# NUMATO_HDR.net
KiCad netlist of a schematic drawn in Altium Designer
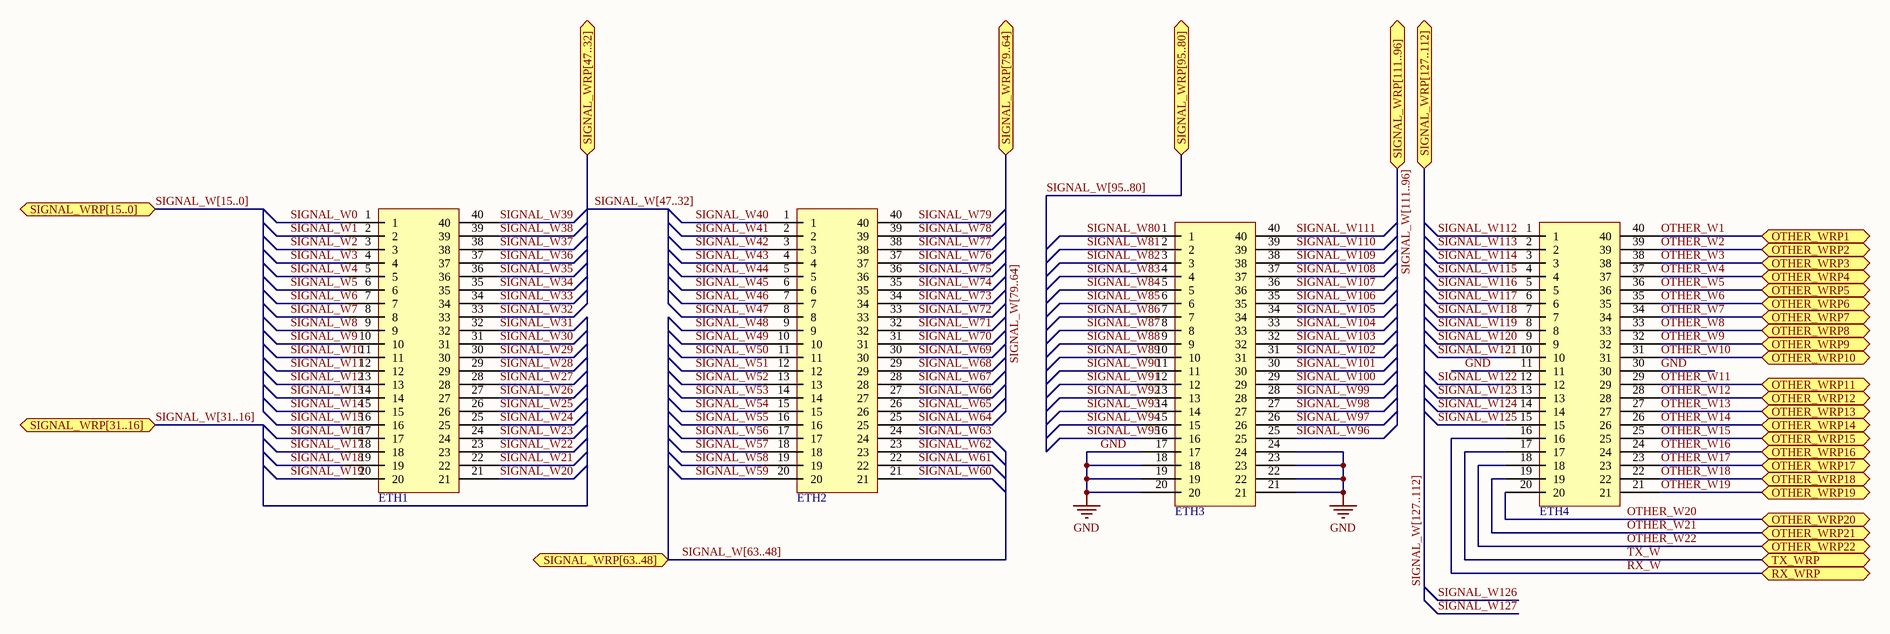
[diagram p0: NUMATO_HDR.SchDoc]

(export (version "E")
  (design (tool "Eeschema 10.0.6"))
  (components
    (comp (ref "ETH1")
      (value "ADAFRUIT_HEADER")
      (footprint "FEMALE_HEADER_SMD")
      (description "Extra tall female header (SMD)")
      (libsource (lib "BBB_Board") (part "ADAFRUIT_HEADER"))
    )
    (comp (ref "ETH2")
      (value "ADAFRUIT_HEADER")
      (footprint "FEMALE_HEADER_SMD")
      (description "Extra tall female header (SMD)")
      (libsource (lib "BBB_Board") (part "ADAFRUIT_HEADER"))
    )
    (comp (ref "ETH3")
      (value "ADAFRUIT_HEADER")
      (footprint "FEMALE_HEADER_SMD")
      (description "Extra tall female header (SMD)")
      (libsource (lib "BBB_Board") (part "ADAFRUIT_HEADER"))
    )
    (comp (ref "ETH4")
      (value "ADAFRUIT_HEADER")
      (footprint "FEMALE_HEADER_SMD")
      (description "Extra tall female header (SMD)")
      (libsource (lib "BBB_Board") (part "ADAFRUIT_HEADER"))
    )
  )
  (nets
    (net (code "1") (name "/OTHER_W1") (class "Default")
      (node (ref "ETH4") (pin "40") (pinfunction "40_40") (pintype "passive"))
    )
    (net (code "2") (name "/OTHER_W2") (class "Default")
      (node (ref "ETH4") (pin "39") (pinfunction "39_39") (pintype "passive"))
    )
    (net (code "3") (name "/OTHER_W3") (class "Default")
      (node (ref "ETH4") (pin "38") (pinfunction "38_38") (pintype "passive"))
    )
    (net (code "4") (name "/OTHER_W4") (class "Default")
      (node (ref "ETH4") (pin "37") (pinfunction "37_37") (pintype "passive"))
    )
    (net (code "5") (name "/OTHER_W5") (class "Default")
      (node (ref "ETH4") (pin "36") (pinfunction "36_36") (pintype "passive"))
    )
    (net (code "6") (name "/OTHER_W6") (class "Default")
      (node (ref "ETH4") (pin "35") (pinfunction "35_35") (pintype "passive"))
    )
    (net (code "7") (name "/OTHER_W7") (class "Default")
      (node (ref "ETH4") (pin "34") (pinfunction "34_34") (pintype "passive"))
    )
    (net (code "8") (name "/OTHER_W8") (class "Default")
      (node (ref "ETH4") (pin "33") (pinfunction "33_33") (pintype "passive"))
    )
    (net (code "9") (name "/OTHER_W9") (class "Default")
      (node (ref "ETH4") (pin "32") (pinfunction "32_32") (pintype "passive"))
    )
    (net (code "10") (name "/OTHER_W10") (class "Default")
      (node (ref "ETH4") (pin "31") (pinfunction "31_31") (pintype "passive"))
    )
    (net (code "11") (name "/OTHER_W11") (class "Default")
      (node (ref "ETH4") (pin "29") (pinfunction "29_29") (pintype "passive"))
    )
    (net (code "12") (name "/OTHER_W12") (class "Default")
      (node (ref "ETH4") (pin "28") (pinfunction "28_28") (pintype "passive"))
    )
    (net (code "13") (name "/OTHER_W13") (class "Default")
      (node (ref "ETH4") (pin "27") (pinfunction "27_27") (pintype "passive"))
    )
    (net (code "14") (name "/OTHER_W14") (class "Default")
      (node (ref "ETH4") (pin "26") (pinfunction "26_26") (pintype "passive"))
    )
    (net (code "15") (name "/OTHER_W15") (class "Default")
      (node (ref "ETH4") (pin "25") (pinfunction "25_25") (pintype "passive"))
    )
    (net (code "16") (name "/OTHER_W16") (class "Default")
      (node (ref "ETH4") (pin "24") (pinfunction "24_24") (pintype "passive"))
    )
    (net (code "17") (name "/OTHER_W17") (class "Default")
      (node (ref "ETH4") (pin "23") (pinfunction "23_23") (pintype "passive"))
    )
    (net (code "18") (name "/OTHER_W18") (class "Default")
      (node (ref "ETH4") (pin "22") (pinfunction "22_22") (pintype "passive"))
    )
    (net (code "19") (name "/OTHER_W19") (class "Default")
      (node (ref "ETH4") (pin "21") (pinfunction "21_21") (pintype "passive"))
    )
    (net (code "20") (name "/OTHER_W20") (class "Default")
      (node (ref "ETH4") (pin "20") (pinfunction "20_20") (pintype "passive"))
    )
    (net (code "21") (name "/OTHER_W21") (class "Default")
      (node (ref "ETH4") (pin "19") (pinfunction "19_19") (pintype "passive"))
    )
    (net (code "22") (name "/OTHER_W22") (class "Default")
      (node (ref "ETH4") (pin "18") (pinfunction "18_18") (pintype "passive"))
    )
    (net (code "23") (name "/RX_W") (class "Default")
      (node (ref "ETH4") (pin "16") (pinfunction "16_16") (pintype "passive"))
    )
    (net (code "24") (name "/SIGNAL_W0") (class "Default")
      (node (ref "ETH1") (pin "1") (pinfunction "1_1") (pintype "passive"))
    )
    (net (code "25") (name "/SIGNAL_W1") (class "Default")
      (node (ref "ETH1") (pin "2") (pinfunction "2_2") (pintype "passive"))
    )
    (net (code "26") (name "/SIGNAL_W2") (class "Default")
      (node (ref "ETH1") (pin "3") (pinfunction "3_3") (pintype "passive"))
    )
    (net (code "27") (name "/SIGNAL_W3") (class "Default")
      (node (ref "ETH1") (pin "4") (pinfunction "4_4") (pintype "passive"))
    )
    (net (code "28") (name "/SIGNAL_W4") (class "Default")
      (node (ref "ETH1") (pin "5") (pinfunction "5_5") (pintype "passive"))
    )
    (net (code "29") (name "/SIGNAL_W5") (class "Default")
      (node (ref "ETH1") (pin "6") (pinfunction "6_6") (pintype "passive"))
    )
    (net (code "30") (name "/SIGNAL_W6") (class "Default")
      (node (ref "ETH1") (pin "7") (pinfunction "7_7") (pintype "passive"))
    )
    (net (code "31") (name "/SIGNAL_W7") (class "Default")
      (node (ref "ETH1") (pin "8") (pinfunction "8_8") (pintype "passive"))
    )
    (net (code "32") (name "/SIGNAL_W8") (class "Default")
      (node (ref "ETH1") (pin "9") (pinfunction "9_9") (pintype "passive"))
    )
    (net (code "33") (name "/SIGNAL_W9") (class "Default")
      (node (ref "ETH1") (pin "10") (pinfunction "10_10") (pintype "passive"))
    )
    (net (code "34") (name "/SIGNAL_W10") (class "Default")
      (node (ref "ETH1") (pin "11") (pinfunction "11_11") (pintype "passive"))
    )
    (net (code "35") (name "/SIGNAL_W11") (class "Default")
      (node (ref "ETH1") (pin "12") (pinfunction "12_12") (pintype "passive"))
    )
    (net (code "36") (name "/SIGNAL_W12") (class "Default")
      (node (ref "ETH1") (pin "13") (pinfunction "13_13") (pintype "passive"))
    )
    (net (code "37") (name "/SIGNAL_W13") (class "Default")
      (node (ref "ETH1") (pin "14") (pinfunction "14_14") (pintype "passive"))
    )
    (net (code "38") (name "/SIGNAL_W14") (class "Default")
      (node (ref "ETH1") (pin "15") (pinfunction "15_15") (pintype "passive"))
    )
    (net (code "39") (name "/SIGNAL_W15") (class "Default")
      (node (ref "ETH1") (pin "16") (pinfunction "16_16") (pintype "passive"))
    )
    (net (code "40") (name "/SIGNAL_W16") (class "Default")
      (node (ref "ETH1") (pin "17") (pinfunction "17_17") (pintype "passive"))
    )
    (net (code "41") (name "/SIGNAL_W17") (class "Default")
      (node (ref "ETH1") (pin "18") (pinfunction "18_18") (pintype "passive"))
    )
    (net (code "42") (name "/SIGNAL_W18") (class "Default")
      (node (ref "ETH1") (pin "19") (pinfunction "19_19") (pintype "passive"))
    )
    (net (code "43") (name "/SIGNAL_W19") (class "Default")
      (node (ref "ETH1") (pin "20") (pinfunction "20_20") (pintype "passive"))
    )
    (net (code "44") (name "/SIGNAL_W20") (class "Default")
      (node (ref "ETH1") (pin "21") (pinfunction "21_21") (pintype "passive"))
    )
    (net (code "45") (name "/SIGNAL_W21") (class "Default")
      (node (ref "ETH1") (pin "22") (pinfunction "22_22") (pintype "passive"))
    )
    (net (code "46") (name "/SIGNAL_W22") (class "Default")
      (node (ref "ETH1") (pin "23") (pinfunction "23_23") (pintype "passive"))
    )
    (net (code "47") (name "/SIGNAL_W23") (class "Default")
      (node (ref "ETH1") (pin "24") (pinfunction "24_24") (pintype "passive"))
    )
    (net (code "48") (name "/SIGNAL_W24") (class "Default")
      (node (ref "ETH1") (pin "25") (pinfunction "25_25") (pintype "passive"))
    )
    (net (code "49") (name "/SIGNAL_W25") (class "Default")
      (node (ref "ETH1") (pin "26") (pinfunction "26_26") (pintype "passive"))
    )
    (net (code "50") (name "/SIGNAL_W26") (class "Default")
      (node (ref "ETH1") (pin "27") (pinfunction "27_27") (pintype "passive"))
    )
    (net (code "51") (name "/SIGNAL_W27") (class "Default")
      (node (ref "ETH1") (pin "28") (pinfunction "28_28") (pintype "passive"))
    )
    (net (code "52") (name "/SIGNAL_W28") (class "Default")
      (node (ref "ETH1") (pin "29") (pinfunction "29_29") (pintype "passive"))
    )
    (net (code "53") (name "/SIGNAL_W29") (class "Default")
      (node (ref "ETH1") (pin "30") (pinfunction "30_30") (pintype "passive"))
    )
    (net (code "54") (name "/SIGNAL_W30") (class "Default")
      (node (ref "ETH1") (pin "31") (pinfunction "31_31") (pintype "passive"))
    )
    (net (code "55") (name "/SIGNAL_W31") (class "Default")
      (node (ref "ETH1") (pin "32") (pinfunction "32_32") (pintype "passive"))
    )
    (net (code "56") (name "/SIGNAL_W32") (class "Default")
      (node (ref "ETH1") (pin "33") (pinfunction "33_33") (pintype "passive"))
    )
    (net (code "57") (name "/SIGNAL_W33") (class "Default")
      (node (ref "ETH1") (pin "34") (pinfunction "34_34") (pintype "passive"))
    )
    (net (code "58") (name "/SIGNAL_W34") (class "Default")
      (node (ref "ETH1") (pin "35") (pinfunction "35_35") (pintype "passive"))
    )
    (net (code "59") (name "/SIGNAL_W35") (class "Default")
      (node (ref "ETH1") (pin "36") (pinfunction "36_36") (pintype "passive"))
    )
    (net (code "60") (name "/SIGNAL_W36") (class "Default")
      (node (ref "ETH1") (pin "37") (pinfunction "37_37") (pintype "passive"))
    )
    (net (code "61") (name "/SIGNAL_W37") (class "Default")
      (node (ref "ETH1") (pin "38") (pinfunction "38_38") (pintype "passive"))
    )
    (net (code "62") (name "/SIGNAL_W38") (class "Default")
      (node (ref "ETH1") (pin "39") (pinfunction "39_39") (pintype "passive"))
    )
    (net (code "63") (name "/SIGNAL_W39") (class "Default")
      (node (ref "ETH1") (pin "40") (pinfunction "40_40") (pintype "passive"))
    )
    (net (code "64") (name "/SIGNAL_W40") (class "Default")
      (node (ref "ETH2") (pin "1") (pinfunction "1_1") (pintype "passive"))
    )
    (net (code "65") (name "/SIGNAL_W41") (class "Default")
      (node (ref "ETH2") (pin "2") (pinfunction "2_2") (pintype "passive"))
    )
    (net (code "66") (name "/SIGNAL_W42") (class "Default")
      (node (ref "ETH2") (pin "3") (pinfunction "3_3") (pintype "passive"))
    )
    (net (code "67") (name "/SIGNAL_W43") (class "Default")
      (node (ref "ETH2") (pin "4") (pinfunction "4_4") (pintype "passive"))
    )
    (net (code "68") (name "/SIGNAL_W44") (class "Default")
      (node (ref "ETH2") (pin "5") (pinfunction "5_5") (pintype "passive"))
    )
    (net (code "69") (name "/SIGNAL_W45") (class "Default")
      (node (ref "ETH2") (pin "6") (pinfunction "6_6") (pintype "passive"))
    )
    (net (code "70") (name "/SIGNAL_W46") (class "Default")
      (node (ref "ETH2") (pin "7") (pinfunction "7_7") (pintype "passive"))
    )
    (net (code "71") (name "/SIGNAL_W47") (class "Default")
      (node (ref "ETH2") (pin "8") (pinfunction "8_8") (pintype "passive"))
    )
    (net (code "72") (name "/SIGNAL_W48") (class "Default")
      (node (ref "ETH2") (pin "9") (pinfunction "9_9") (pintype "passive"))
    )
    (net (code "73") (name "/SIGNAL_W49") (class "Default")
      (node (ref "ETH2") (pin "10") (pinfunction "10_10") (pintype "passive"))
    )
    (net (code "74") (name "/SIGNAL_W50") (class "Default")
      (node (ref "ETH2") (pin "11") (pinfunction "11_11") (pintype "passive"))
    )
    (net (code "75") (name "/SIGNAL_W51") (class "Default")
      (node (ref "ETH2") (pin "12") (pinfunction "12_12") (pintype "passive"))
    )
    (net (code "76") (name "/SIGNAL_W52") (class "Default")
      (node (ref "ETH2") (pin "13") (pinfunction "13_13") (pintype "passive"))
    )
    (net (code "77") (name "/SIGNAL_W53") (class "Default")
      (node (ref "ETH2") (pin "14") (pinfunction "14_14") (pintype "passive"))
    )
    (net (code "78") (name "/SIGNAL_W54") (class "Default")
      (node (ref "ETH2") (pin "15") (pinfunction "15_15") (pintype "passive"))
    )
    (net (code "79") (name "/SIGNAL_W55") (class "Default")
      (node (ref "ETH2") (pin "16") (pinfunction "16_16") (pintype "passive"))
    )
    (net (code "80") (name "/SIGNAL_W56") (class "Default")
      (node (ref "ETH2") (pin "17") (pinfunction "17_17") (pintype "passive"))
    )
    (net (code "81") (name "/SIGNAL_W57") (class "Default")
      (node (ref "ETH2") (pin "18") (pinfunction "18_18") (pintype "passive"))
    )
    (net (code "82") (name "/SIGNAL_W58") (class "Default")
      (node (ref "ETH2") (pin "19") (pinfunction "19_19") (pintype "passive"))
    )
    (net (code "83") (name "/SIGNAL_W59") (class "Default")
      (node (ref "ETH2") (pin "20") (pinfunction "20_20") (pintype "passive"))
    )
    (net (code "84") (name "/SIGNAL_W60") (class "Default")
      (node (ref "ETH2") (pin "21") (pinfunction "21_21") (pintype "passive"))
    )
    (net (code "85") (name "/SIGNAL_W61") (class "Default")
      (node (ref "ETH2") (pin "22") (pinfunction "22_22") (pintype "passive"))
    )
    (net (code "86") (name "/SIGNAL_W62") (class "Default")
      (node (ref "ETH2") (pin "23") (pinfunction "23_23") (pintype "passive"))
    )
    (net (code "87") (name "/SIGNAL_W63") (class "Default")
      (node (ref "ETH2") (pin "24") (pinfunction "24_24") (pintype "passive"))
    )
    (net (code "88") (name "/SIGNAL_W64") (class "Default")
      (node (ref "ETH2") (pin "25") (pinfunction "25_25") (pintype "passive"))
    )
    (net (code "89") (name "/SIGNAL_W65") (class "Default")
      (node (ref "ETH2") (pin "26") (pinfunction "26_26") (pintype "passive"))
    )
    (net (code "90") (name "/SIGNAL_W66") (class "Default")
      (node (ref "ETH2") (pin "27") (pinfunction "27_27") (pintype "passive"))
    )
    (net (code "91") (name "/SIGNAL_W67") (class "Default")
      (node (ref "ETH2") (pin "28") (pinfunction "28_28") (pintype "passive"))
    )
    (net (code "92") (name "/SIGNAL_W68") (class "Default")
      (node (ref "ETH2") (pin "29") (pinfunction "29_29") (pintype "passive"))
    )
    (net (code "93") (name "/SIGNAL_W69") (class "Default")
      (node (ref "ETH2") (pin "30") (pinfunction "30_30") (pintype "passive"))
    )
    (net (code "94") (name "/SIGNAL_W70") (class "Default")
      (node (ref "ETH2") (pin "31") (pinfunction "31_31") (pintype "passive"))
    )
    (net (code "95") (name "/SIGNAL_W71") (class "Default")
      (node (ref "ETH2") (pin "32") (pinfunction "32_32") (pintype "passive"))
    )
    (net (code "96") (name "/SIGNAL_W72") (class "Default")
      (node (ref "ETH2") (pin "33") (pinfunction "33_33") (pintype "passive"))
    )
    (net (code "97") (name "/SIGNAL_W73") (class "Default")
      (node (ref "ETH2") (pin "34") (pinfunction "34_34") (pintype "passive"))
    )
    (net (code "98") (name "/SIGNAL_W74") (class "Default")
      (node (ref "ETH2") (pin "35") (pinfunction "35_35") (pintype "passive"))
    )
    (net (code "99") (name "/SIGNAL_W75") (class "Default")
      (node (ref "ETH2") (pin "36") (pinfunction "36_36") (pintype "passive"))
    )
    (net (code "100") (name "/SIGNAL_W76") (class "Default")
      (node (ref "ETH2") (pin "37") (pinfunction "37_37") (pintype "passive"))
    )
    (net (code "101") (name "/SIGNAL_W77") (class "Default")
      (node (ref "ETH2") (pin "38") (pinfunction "38_38") (pintype "passive"))
    )
    (net (code "102") (name "/SIGNAL_W78") (class "Default")
      (node (ref "ETH2") (pin "39") (pinfunction "39_39") (pintype "passive"))
    )
    (net (code "103") (name "/SIGNAL_W79") (class "Default")
      (node (ref "ETH2") (pin "40") (pinfunction "40_40") (pintype "passive"))
    )
    (net (code "104") (name "/SIGNAL_W80") (class "Default")
      (node (ref "ETH3") (pin "1") (pinfunction "1_1") (pintype "passive"))
    )
    (net (code "105") (name "/SIGNAL_W81") (class "Default")
      (node (ref "ETH3") (pin "2") (pinfunction "2_2") (pintype "passive"))
    )
    (net (code "106") (name "/SIGNAL_W82") (class "Default")
      (node (ref "ETH3") (pin "3") (pinfunction "3_3") (pintype "passive"))
    )
    (net (code "107") (name "/SIGNAL_W83") (class "Default")
      (node (ref "ETH3") (pin "4") (pinfunction "4_4") (pintype "passive"))
    )
    (net (code "108") (name "/SIGNAL_W84") (class "Default")
      (node (ref "ETH3") (pin "5") (pinfunction "5_5") (pintype "passive"))
    )
    (net (code "109") (name "/SIGNAL_W85") (class "Default")
      (node (ref "ETH3") (pin "6") (pinfunction "6_6") (pintype "passive"))
    )
    (net (code "110") (name "/SIGNAL_W86") (class "Default")
      (node (ref "ETH3") (pin "7") (pinfunction "7_7") (pintype "passive"))
    )
    (net (code "111") (name "/SIGNAL_W87") (class "Default")
      (node (ref "ETH3") (pin "8") (pinfunction "8_8") (pintype "passive"))
    )
    (net (code "112") (name "/SIGNAL_W88") (class "Default")
      (node (ref "ETH3") (pin "9") (pinfunction "9_9") (pintype "passive"))
    )
    (net (code "113") (name "/SIGNAL_W89") (class "Default")
      (node (ref "ETH3") (pin "10") (pinfunction "10_10") (pintype "passive"))
    )
    (net (code "114") (name "/SIGNAL_W90") (class "Default")
      (node (ref "ETH3") (pin "11") (pinfunction "11_11") (pintype "passive"))
    )
    (net (code "115") (name "/SIGNAL_W91") (class "Default")
      (node (ref "ETH3") (pin "12") (pinfunction "12_12") (pintype "passive"))
    )
    (net (code "116") (name "/SIGNAL_W92") (class "Default")
      (node (ref "ETH3") (pin "13") (pinfunction "13_13") (pintype "passive"))
    )
    (net (code "117") (name "/SIGNAL_W93") (class "Default")
      (node (ref "ETH3") (pin "14") (pinfunction "14_14") (pintype "passive"))
    )
    (net (code "118") (name "/SIGNAL_W94") (class "Default")
      (node (ref "ETH3") (pin "15") (pinfunction "15_15") (pintype "passive"))
    )
    (net (code "119") (name "/SIGNAL_W95") (class "Default")
      (node (ref "ETH3") (pin "16") (pinfunction "16_16") (pintype "passive"))
    )
    (net (code "120") (name "/SIGNAL_W96") (class "Default")
      (node (ref "ETH3") (pin "25") (pinfunction "25_25") (pintype "passive"))
    )
    (net (code "121") (name "/SIGNAL_W97") (class "Default")
      (node (ref "ETH3") (pin "26") (pinfunction "26_26") (pintype "passive"))
    )
    (net (code "122") (name "/SIGNAL_W98") (class "Default")
      (node (ref "ETH3") (pin "27") (pinfunction "27_27") (pintype "passive"))
    )
    (net (code "123") (name "/SIGNAL_W99") (class "Default")
      (node (ref "ETH3") (pin "28") (pinfunction "28_28") (pintype "passive"))
    )
    (net (code "124") (name "/SIGNAL_W100") (class "Default")
      (node (ref "ETH3") (pin "29") (pinfunction "29_29") (pintype "passive"))
    )
    (net (code "125") (name "/SIGNAL_W101") (class "Default")
      (node (ref "ETH3") (pin "30") (pinfunction "30_30") (pintype "passive"))
    )
    (net (code "126") (name "/SIGNAL_W102") (class "Default")
      (node (ref "ETH3") (pin "31") (pinfunction "31_31") (pintype "passive"))
    )
    (net (code "127") (name "/SIGNAL_W103") (class "Default")
      (node (ref "ETH3") (pin "32") (pinfunction "32_32") (pintype "passive"))
    )
    (net (code "128") (name "/SIGNAL_W104") (class "Default")
      (node (ref "ETH3") (pin "33") (pinfunction "33_33") (pintype "passive"))
    )
    (net (code "129") (name "/SIGNAL_W105") (class "Default")
      (node (ref "ETH3") (pin "34") (pinfunction "34_34") (pintype "passive"))
    )
    (net (code "130") (name "/SIGNAL_W106") (class "Default")
      (node (ref "ETH3") (pin "35") (pinfunction "35_35") (pintype "passive"))
    )
    (net (code "131") (name "/SIGNAL_W107") (class "Default")
      (node (ref "ETH3") (pin "36") (pinfunction "36_36") (pintype "passive"))
    )
    (net (code "132") (name "/SIGNAL_W108") (class "Default")
      (node (ref "ETH3") (pin "37") (pinfunction "37_37") (pintype "passive"))
    )
    (net (code "133") (name "/SIGNAL_W109") (class "Default")
      (node (ref "ETH3") (pin "38") (pinfunction "38_38") (pintype "passive"))
    )
    (net (code "134") (name "/SIGNAL_W110") (class "Default")
      (node (ref "ETH3") (pin "39") (pinfunction "39_39") (pintype "passive"))
    )
    (net (code "135") (name "/SIGNAL_W111") (class "Default")
      (node (ref "ETH3") (pin "40") (pinfunction "40_40") (pintype "passive"))
    )
    (net (code "136") (name "/SIGNAL_W112") (class "Default")
      (node (ref "ETH4") (pin "1") (pinfunction "1_1") (pintype "passive"))
    )
    (net (code "137") (name "/SIGNAL_W113") (class "Default")
      (node (ref "ETH4") (pin "2") (pinfunction "2_2") (pintype "passive"))
    )
    (net (code "138") (name "/SIGNAL_W114") (class "Default")
      (node (ref "ETH4") (pin "3") (pinfunction "3_3") (pintype "passive"))
    )
    (net (code "139") (name "/SIGNAL_W115") (class "Default")
      (node (ref "ETH4") (pin "4") (pinfunction "4_4") (pintype "passive"))
    )
    (net (code "140") (name "/SIGNAL_W116") (class "Default")
      (node (ref "ETH4") (pin "5") (pinfunction "5_5") (pintype "passive"))
    )
    (net (code "141") (name "/SIGNAL_W117") (class "Default")
      (node (ref "ETH4") (pin "6") (pinfunction "6_6") (pintype "passive"))
    )
    (net (code "142") (name "/SIGNAL_W118") (class "Default")
      (node (ref "ETH4") (pin "7") (pinfunction "7_7") (pintype "passive"))
    )
    (net (code "143") (name "/SIGNAL_W119") (class "Default")
      (node (ref "ETH4") (pin "8") (pinfunction "8_8") (pintype "passive"))
    )
    (net (code "144") (name "/SIGNAL_W120") (class "Default")
      (node (ref "ETH4") (pin "9") (pinfunction "9_9") (pintype "passive"))
    )
    (net (code "145") (name "/SIGNAL_W121") (class "Default")
      (node (ref "ETH4") (pin "10") (pinfunction "10_10") (pintype "passive"))
    )
    (net (code "146") (name "/SIGNAL_W122") (class "Default")
      (node (ref "ETH4") (pin "12") (pinfunction "12_12") (pintype "passive"))
    )
    (net (code "147") (name "/SIGNAL_W123") (class "Default")
      (node (ref "ETH4") (pin "13") (pinfunction "13_13") (pintype "passive"))
    )
    (net (code "148") (name "/SIGNAL_W124") (class "Default")
      (node (ref "ETH4") (pin "14") (pinfunction "14_14") (pintype "passive"))
    )
    (net (code "149") (name "/SIGNAL_W125") (class "Default")
      (node (ref "ETH4") (pin "15") (pinfunction "15_15") (pintype "passive"))
    )
    (net (code "160") (name "/TX_W") (class "Default")
      (node (ref "ETH4") (pin "17") (pinfunction "17_17") (pintype "passive"))
    )
    (net (code "161") (name "GND") (class "Default")
      (node (ref "ETH3") (pin "17") (pinfunction "17_17") (pintype "passive"))
      (node (ref "ETH3") (pin "18") (pinfunction "18_18") (pintype "passive"))
      (node (ref "ETH3") (pin "19") (pinfunction "19_19") (pintype "passive"))
      (node (ref "ETH3") (pin "20") (pinfunction "20_20") (pintype "passive"))
      (node (ref "ETH3") (pin "21") (pinfunction "21_21") (pintype "passive"))
      (node (ref "ETH3") (pin "22") (pinfunction "22_22") (pintype "passive"))
      (node (ref "ETH3") (pin "23") (pinfunction "23_23") (pintype "passive"))
      (node (ref "ETH3") (pin "24") (pinfunction "24_24") (pintype "passive"))
      (node (ref "ETH4") (pin "11") (pinfunction "11_11") (pintype "passive"))
      (node (ref "ETH4") (pin "30") (pinfunction "30_30") (pintype "passive"))
    )
  )
)
